# Microcontroller.net
KiCad netlist of a schematic drawn in Altium Designer
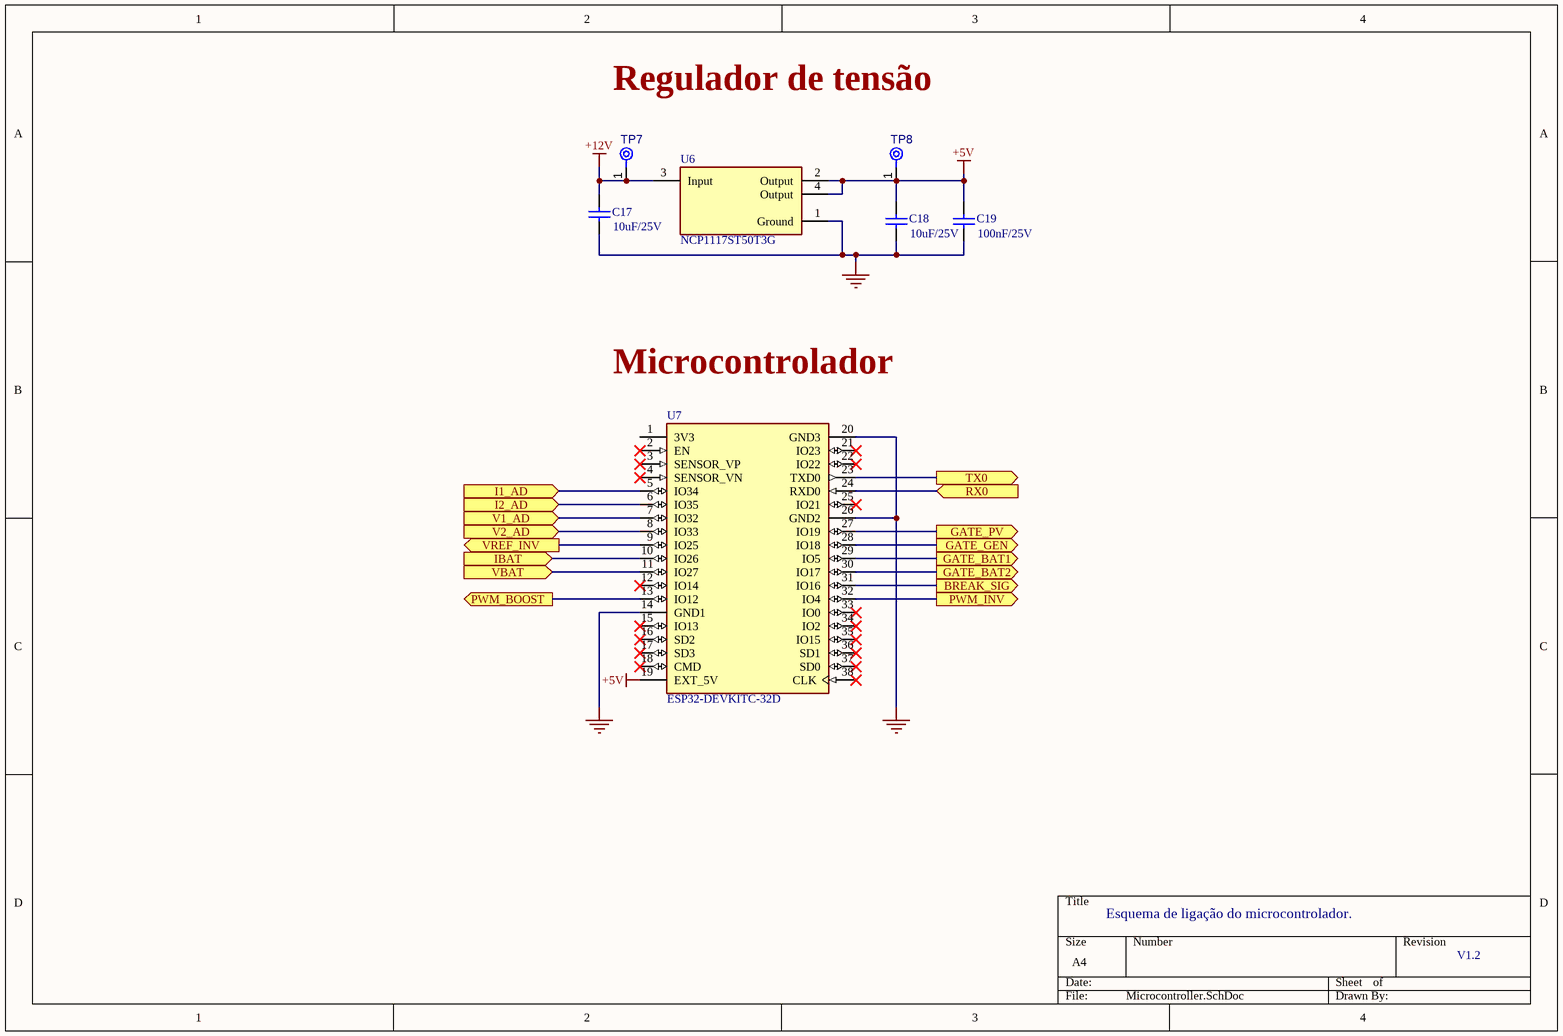
[diagram p0: Microcontroller.SchDoc]

(export (version "E")
  (design (tool "Eeschema 10.0.6"))
  (components
    (comp (ref "C17")
      (value "10uF/25V")
      (footprint "C1206")
      (description "Cap Ceramic 10uF 25V X7R 20% Pad SMD 1206 125C Automotive T/R")
      (fields
        (field (name "MANUFACTURER") "KEMET")
        (field (name "MANUFACTURER PART NUMBER") "C1206C106M3RACAUTO")
        (field (name "PUBLISHER") "Altium Limited")
      )
      (libsource (lib "Miscellaneous Devices") (part "Cap Semi"))
    )
    (comp (ref "C18")
      (value "10uF/25V")
      (footprint "C1206")
      (description "Cap Ceramic 10uF 25V X7R 20% Pad SMD 1206 125C Automotive T/R")
      (fields
        (field (name "MANUFACTURER") "KEMET")
        (field (name "MANUFACTURER PART NUMBER") "C1206C106M3RACAUTO")
        (field (name "PUBLISHER") "Altium Limited")
      )
      (libsource (lib "Miscellaneous Devices") (part "Cap Semi"))
    )
    (comp (ref "C19")
      (value "100nF/25V")
      (footprint "C1206")
      (description "CAP CER 1206 0.1UF 25V C0G 5%")
      (fields
        (field (name "MANUFACTURER") "KEMET")
        (field (name "MANUFACTURER PART NUMBER") "C1206C104J3GEC7210")
        (field (name "PUBLISHER") "Altium Limited")
      )
      (libsource (lib "Miscellaneous Devices") (part "Cap Semi"))
    )
    (comp (ref "TP7")
      (value "TPAD6R")
      (footprint "TP06R")
      (description "0.6mm round")
      (libsource (lib "PI2") (part "CMP-001-0001-4"))
    )
    (comp (ref "TP8")
      (value "TPAD6R")
      (footprint "TP06R")
      (description "0.6mm round")
      (libsource (lib "PI2") (part "CMP-001-0001-4"))
    )
    (comp (ref "U6")
      (value "NCP1117ST50T3G")
      (footprint "FP-318H-MFG")
      (description "IC REG LINEAR 5V 1A SOT223")
      (fields (field (name "TOLERANCE") "1%") (field (name "MANUFACTURER") "ON Semiconductor"))
      (libsource (lib "Altium Content Vault") (part "193b6ed835dfa032b90f0234c0cf79c"))
    )
    (comp (ref "U7")
      (value "ESP32-DEVKITC-32D")
      (footprint "MODULE_ESP32-DEVKITC-32D")
      (description "Espressif Systems ESP32-DevKitC Microcontroller")
      (fields (field (name "MF") "Espressif Systems"))
      (libsource (lib "pi2") (part "ESP32-DEVKITC-32D"))
    )
  )
  (nets
    (net (code "1") (name "+5V") (class "Default")
      (node (ref "C18") (pin "2") (pinfunction "2_2") (pintype "passive"))
      (node (ref "C19") (pin "2") (pinfunction "2_2") (pintype "passive"))
      (node (ref "TP8") (pin "1") (pinfunction "TP_1") (pintype "passive"))
      (node (ref "U6") (pin "2") (pinfunction "Output_2") (pintype "power_in"))
      (node (ref "U6") (pin "4") (pinfunction "Output_4") (pintype "power_in"))
      (node (ref "U7") (pin "19") (pinfunction "EXT_5V_19") (pintype "power_in"))
    )
    (net (code "2") (name "+12V") (class "Default")
      (node (ref "C17") (pin "2") (pinfunction "2_2") (pintype "passive"))
      (node (ref "TP7") (pin "1") (pinfunction "TP_1") (pintype "passive"))
      (node (ref "U6") (pin "3") (pinfunction "Input_3") (pintype "power_in"))
    )
    (net (code "3") (name "/BREAK_SIG") (class "Default")
      (node (ref "U7") (pin "31") (pinfunction "IO16_31") (pintype "bidirectional"))
    )
    (net (code "4") (name "/GATE_BAT1") (class "Default")
      (node (ref "U7") (pin "29") (pinfunction "IO5_29") (pintype "bidirectional"))
    )
    (net (code "5") (name "/GATE_BAT2") (class "Default")
      (node (ref "U7") (pin "30") (pinfunction "IO17_30") (pintype "bidirectional"))
    )
    (net (code "6") (name "/GATE_GEN") (class "Default")
      (node (ref "U7") (pin "28") (pinfunction "IO18_28") (pintype "bidirectional"))
    )
    (net (code "7") (name "/GATE_PV") (class "Default")
      (node (ref "U7") (pin "27") (pinfunction "IO19_27") (pintype "bidirectional"))
    )
    (net (code "8") (name "/I1_AD") (class "Default")
      (node (ref "U7") (pin "5") (pinfunction "IO34_5") (pintype "bidirectional"))
    )
    (net (code "9") (name "/I2_AD") (class "Default")
      (node (ref "U7") (pin "6") (pinfunction "IO35_6") (pintype "bidirectional"))
    )
    (net (code "10") (name "/IBAT") (class "Default")
      (node (ref "U7") (pin "10") (pinfunction "IO26_10") (pintype "bidirectional"))
    )
    (net (code "11") (name "/PWM_BOOST") (class "Default")
      (node (ref "U7") (pin "13") (pinfunction "IO12_13") (pintype "bidirectional"))
    )
    (net (code "12") (name "/PWM_INV") (class "Default")
      (node (ref "U7") (pin "32") (pinfunction "IO4_32") (pintype "bidirectional"))
    )
    (net (code "13") (name "/RX0") (class "Default")
      (node (ref "U7") (pin "24") (pinfunction "RXD0_24") (pintype "input"))
    )
    (net (code "14") (name "/TX0") (class "Default")
      (node (ref "U7") (pin "23") (pinfunction "TXD0_23") (pintype "output"))
    )
    (net (code "15") (name "/V1_AD") (class "Default")
      (node (ref "U7") (pin "7") (pinfunction "IO32_7") (pintype "bidirectional"))
    )
    (net (code "16") (name "/V2_AD") (class "Default")
      (node (ref "U7") (pin "8") (pinfunction "IO33_8") (pintype "bidirectional"))
    )
    (net (code "17") (name "/VBAT") (class "Default")
      (node (ref "U7") (pin "11") (pinfunction "IO27_11") (pintype "bidirectional"))
    )
    (net (code "18") (name "/VREF_INV") (class "Default")
      (node (ref "U7") (pin "9") (pinfunction "IO25_9") (pintype "bidirectional"))
    )
    (net (code "19") (name "GND") (class "Default")
      (node (ref "C17") (pin "1") (pinfunction "1_1") (pintype "passive"))
      (node (ref "C18") (pin "1") (pinfunction "1_1") (pintype "passive"))
      (node (ref "C19") (pin "1") (pinfunction "1_1") (pintype "passive"))
      (node (ref "U6") (pin "1") (pinfunction "Ground_1") (pintype "power_in"))
      (node (ref "U7") (pin "14") (pinfunction "GND1_14") (pintype "power_in"))
      (node (ref "U7") (pin "20") (pinfunction "GND3_20") (pintype "power_in"))
      (node (ref "U7") (pin "26") (pinfunction "GND2_26") (pintype "power_in"))
    )
    (net (code "20") (name "unconnected-(U7-3V3-Pad1)") (class "Default")
      (node (ref "U7") (pin "1") (pinfunction "3V3_1") (pintype "power_in"))
    )
    (net (code "21") (name "unconnected-(U7-CLK-Pad38)") (class "Default")
      (node (ref "U7") (pin "38") (pinfunction "CLK_38") (pintype "input+no_connect"))
    )
    (net (code "22") (name "unconnected-(U7-CMD-Pad18)") (class "Default")
      (node (ref "U7") (pin "18") (pinfunction "CMD_18") (pintype "bidirectional+no_connect"))
    )
    (net (code "23") (name "unconnected-(U7-EN-Pad2)") (class "Default")
      (node (ref "U7") (pin "2") (pinfunction "EN_2") (pintype "input+no_connect"))
    )
    (net (code "24") (name "unconnected-(U7-IO0-Pad33)") (class "Default")
      (node (ref "U7") (pin "33") (pinfunction "IO0_33") (pintype "bidirectional+no_connect"))
    )
    (net (code "25") (name "unconnected-(U7-IO2-Pad34)") (class "Default")
      (node (ref "U7") (pin "34") (pinfunction "IO2_34") (pintype "bidirectional+no_connect"))
    )
    (net (code "26") (name "unconnected-(U7-IO13-Pad15)") (class "Default")
      (node (ref "U7") (pin "15") (pinfunction "IO13_15") (pintype "bidirectional+no_connect"))
    )
    (net (code "27") (name "unconnected-(U7-IO14-Pad12)") (class "Default")
      (node (ref "U7") (pin "12") (pinfunction "IO14_12") (pintype "bidirectional+no_connect"))
    )
    (net (code "28") (name "unconnected-(U7-IO15-Pad35)") (class "Default")
      (node (ref "U7") (pin "35") (pinfunction "IO15_35") (pintype "bidirectional+no_connect"))
    )
    (net (code "29") (name "unconnected-(U7-IO21-Pad25)") (class "Default")
      (node (ref "U7") (pin "25") (pinfunction "IO21_25") (pintype "bidirectional+no_connect"))
    )
    (net (code "30") (name "unconnected-(U7-IO22-Pad22)") (class "Default")
      (node (ref "U7") (pin "22") (pinfunction "IO22_22") (pintype "bidirectional+no_connect"))
    )
    (net (code "31") (name "unconnected-(U7-IO23-Pad21)") (class "Default")
      (node (ref "U7") (pin "21") (pinfunction "IO23_21") (pintype "bidirectional+no_connect"))
    )
    (net (code "32") (name "unconnected-(U7-SD0-Pad37)") (class "Default")
      (node (ref "U7") (pin "37") (pinfunction "SD0_37") (pintype "bidirectional+no_connect"))
    )
    (net (code "33") (name "unconnected-(U7-SD1-Pad36)") (class "Default")
      (node (ref "U7") (pin "36") (pinfunction "SD1_36") (pintype "bidirectional+no_connect"))
    )
    (net (code "34") (name "unconnected-(U7-SD2-Pad16)") (class "Default")
      (node (ref "U7") (pin "16") (pinfunction "SD2_16") (pintype "bidirectional+no_connect"))
    )
    (net (code "35") (name "unconnected-(U7-SD3-Pad17)") (class "Default")
      (node (ref "U7") (pin "17") (pinfunction "SD3_17") (pintype "bidirectional+no_connect"))
    )
    (net (code "36") (name "unconnected-(U7-SENSOR_VN-Pad4)") (class "Default")
      (node (ref "U7") (pin "4") (pinfunction "SENSOR_VN_4") (pintype "input+no_connect"))
    )
    (net (code "37") (name "unconnected-(U7-SENSOR_VP-Pad3)") (class "Default")
      (node (ref "U7") (pin "3") (pinfunction "SENSOR_VP_3") (pintype "input+no_connect"))
    )
  )
)
